# chart.net
KiCad netlist of a schematic drawn in EAGLE
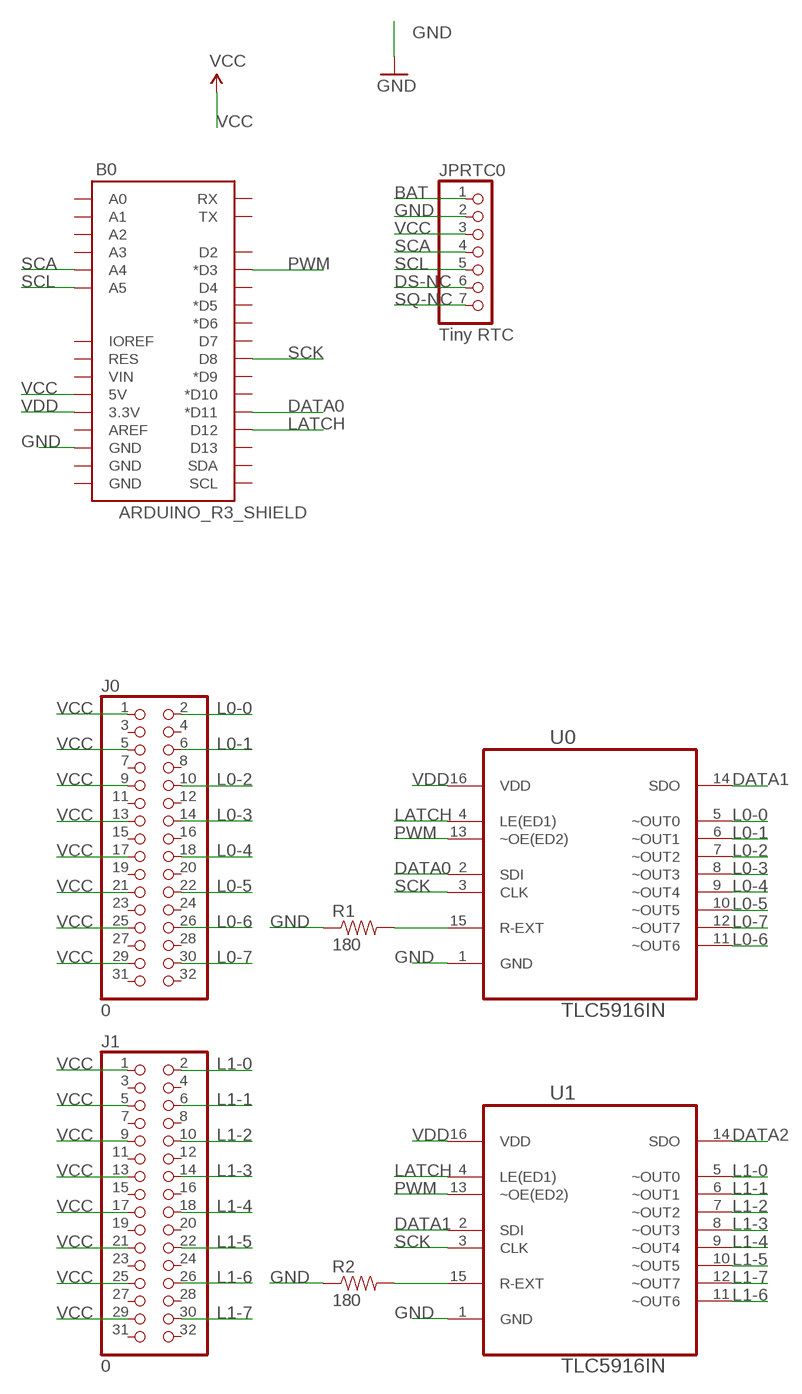
[diagram p0: schematic, sheet 1]

(export (version "E")
  (design (tool "Eeschema 10.0.6"))
  (components
    (comp (ref "B0")
      (value "ARDUINO_R3_SHIELD")
      (footprint "eagle-import:UNO_R3_SHIELD")
      (libsource (lib "eagle-import") (part "ARDUINO_R3_SHIELD"))
    )
    (comp (ref "J0")
      (value "0")
      (footprint "eagle-import:2X16")
      (libsource (lib "eagle-import") (part "PINHD-2X16"))
    )
    (comp (ref "J1")
      (value "0")
      (footprint "eagle-import:2X16")
      (libsource (lib "eagle-import") (part "PINHD-2X16"))
    )
    (comp (ref "JPRTC0")
      (value "Tiny RTC")
      (footprint "eagle-import:1X07")
      (libsource (lib "eagle-import") (part "PINHD-1X7"))
    )
    (comp (ref "R1")
      (value "180")
      (footprint "eagle-import:AXIAL-0.4")
      (libsource (lib "eagle-import") (part "RESISTORPTH-1/4W"))
    )
    (comp (ref "R2")
      (value "180")
      (footprint "eagle-import:AXIAL-0.4")
      (libsource (lib "eagle-import") (part "RESISTORPTH-1/4W"))
    )
    (comp (ref "U0")
      (value "TLC5916IN")
      (footprint "eagle-import:DIP254P762X508-16")
      (libsource (lib "eagle-import") (part "TLC5916IN"))
    )
    (comp (ref "U1")
      (value "TLC5916IN")
      (footprint "eagle-import:DIP254P762X508-16")
      (libsource (lib "eagle-import") (part "TLC5916IN"))
    )
  )
  (nets
    (net (code "1") (name "/BAT") (class "Default")
      (node (ref "JPRTC0") (pin "1") (pinfunction "1_1") (pintype "passive"))
    )
    (net (code "2") (name "/DATA0") (class "Default")
      (node (ref "B0") (pin "D11") (pinfunction "*D11_D11") (pintype "bidirectional"))
      (node (ref "U0") (pin "2") (pinfunction "SDI_2") (pintype "input"))
    )
    (net (code "3") (name "/DATA1") (class "Default")
      (node (ref "U0") (pin "14") (pinfunction "SDO_14") (pintype "output"))
      (node (ref "U1") (pin "2") (pinfunction "SDI_2") (pintype "input"))
    )
    (net (code "4") (name "/DATA2") (class "Default")
      (node (ref "U1") (pin "14") (pinfunction "SDO_14") (pintype "output"))
    )
    (net (code "5") (name "/DS-NC") (class "Default")
      (node (ref "JPRTC0") (pin "6") (pinfunction "6_6") (pintype "passive"))
    )
    (net (code "6") (name "/L0-0") (class "Default")
      (node (ref "J0") (pin "2") (pinfunction "2_2") (pintype "passive"))
      (node (ref "U0") (pin "5") (pinfunction "~{OUT0}_5") (pintype "output"))
    )
    (net (code "7") (name "/L0-1") (class "Default")
      (node (ref "J0") (pin "6") (pinfunction "6_6") (pintype "passive"))
      (node (ref "U0") (pin "6") (pinfunction "~{OUT1}_6") (pintype "output"))
    )
    (net (code "8") (name "/L0-2") (class "Default")
      (node (ref "J0") (pin "10") (pinfunction "10_10") (pintype "passive"))
      (node (ref "U0") (pin "7") (pinfunction "~{OUT2}_7") (pintype "output"))
    )
    (net (code "9") (name "/L0-3") (class "Default")
      (node (ref "J0") (pin "14") (pinfunction "14_14") (pintype "passive"))
      (node (ref "U0") (pin "8") (pinfunction "~{OUT3}_8") (pintype "output"))
    )
    (net (code "10") (name "/L0-4") (class "Default")
      (node (ref "J0") (pin "18") (pinfunction "18_18") (pintype "passive"))
      (node (ref "U0") (pin "9") (pinfunction "~{OUT4}_9") (pintype "output"))
    )
    (net (code "11") (name "/L0-5") (class "Default")
      (node (ref "J0") (pin "22") (pinfunction "22_22") (pintype "passive"))
      (node (ref "U0") (pin "10") (pinfunction "~{OUT5}_10") (pintype "output"))
    )
    (net (code "12") (name "/L0-6") (class "Default")
      (node (ref "J0") (pin "26") (pinfunction "26_26") (pintype "passive"))
      (node (ref "U0") (pin "11") (pinfunction "~{OUT6}_11") (pintype "output"))
    )
    (net (code "13") (name "/L0-7") (class "Default")
      (node (ref "J0") (pin "30") (pinfunction "30_30") (pintype "passive"))
      (node (ref "U0") (pin "12") (pinfunction "~{OUT7}_12") (pintype "output"))
    )
    (net (code "14") (name "/L1-0") (class "Default")
      (node (ref "J1") (pin "2") (pinfunction "2_2") (pintype "passive"))
      (node (ref "U1") (pin "5") (pinfunction "~{OUT0}_5") (pintype "output"))
    )
    (net (code "15") (name "/L1-1") (class "Default")
      (node (ref "J1") (pin "6") (pinfunction "6_6") (pintype "passive"))
      (node (ref "U1") (pin "6") (pinfunction "~{OUT1}_6") (pintype "output"))
    )
    (net (code "16") (name "/L1-2") (class "Default")
      (node (ref "J1") (pin "10") (pinfunction "10_10") (pintype "passive"))
      (node (ref "U1") (pin "7") (pinfunction "~{OUT2}_7") (pintype "output"))
    )
    (net (code "17") (name "/L1-3") (class "Default")
      (node (ref "J1") (pin "14") (pinfunction "14_14") (pintype "passive"))
      (node (ref "U1") (pin "8") (pinfunction "~{OUT3}_8") (pintype "output"))
    )
    (net (code "18") (name "/L1-4") (class "Default")
      (node (ref "J1") (pin "18") (pinfunction "18_18") (pintype "passive"))
      (node (ref "U1") (pin "9") (pinfunction "~{OUT4}_9") (pintype "output"))
    )
    (net (code "19") (name "/L1-5") (class "Default")
      (node (ref "J1") (pin "22") (pinfunction "22_22") (pintype "passive"))
      (node (ref "U1") (pin "10") (pinfunction "~{OUT5}_10") (pintype "output"))
    )
    (net (code "20") (name "/L1-6") (class "Default")
      (node (ref "J1") (pin "26") (pinfunction "26_26") (pintype "passive"))
      (node (ref "U1") (pin "11") (pinfunction "~{OUT6}_11") (pintype "output"))
    )
    (net (code "21") (name "/L1-7") (class "Default")
      (node (ref "J1") (pin "30") (pinfunction "30_30") (pintype "passive"))
      (node (ref "U1") (pin "12") (pinfunction "~{OUT7}_12") (pintype "output"))
    )
    (net (code "22") (name "/LATCH") (class "Default")
      (node (ref "B0") (pin "D12") (pinfunction "D12_D12") (pintype "bidirectional"))
      (node (ref "U0") (pin "4") (pinfunction "LE(ED1)_4") (pintype "input"))
      (node (ref "U1") (pin "4") (pinfunction "LE(ED1)_4") (pintype "input"))
    )
    (net (code "23") (name "/PWM") (class "Default")
      (node (ref "B0") (pin "D3") (pinfunction "*D3_D3") (pintype "bidirectional"))
      (node (ref "U0") (pin "13") (pinfunction "~{OE(ED2})_13") (pintype "input"))
      (node (ref "U1") (pin "13") (pinfunction "~{OE(ED2})_13") (pintype "input"))
    )
    (net (code "24") (name "/SCA") (class "Default")
      (node (ref "B0") (pin "A4") (pinfunction "A4_A4") (pintype "bidirectional"))
      (node (ref "JPRTC0") (pin "4") (pinfunction "4_4") (pintype "passive"))
    )
    (net (code "25") (name "/SCK") (class "Default")
      (node (ref "B0") (pin "D8") (pinfunction "D8_D8") (pintype "bidirectional"))
      (node (ref "U0") (pin "3") (pinfunction "CLK_3") (pintype "input"))
      (node (ref "U1") (pin "3") (pinfunction "CLK_3") (pintype "input"))
    )
    (net (code "26") (name "/SCL") (class "Default")
      (node (ref "B0") (pin "A5") (pinfunction "A5_A5") (pintype "bidirectional"))
      (node (ref "JPRTC0") (pin "5") (pinfunction "5_5") (pintype "passive"))
    )
    (net (code "27") (name "/SQ-NC") (class "Default")
      (node (ref "JPRTC0") (pin "7") (pinfunction "7_7") (pintype "passive"))
    )
    (net (code "28") (name "/VDD") (class "Default")
      (node (ref "B0") (pin "3.3V") (pinfunction "3.3V_3.3V") (pintype "bidirectional"))
      (node (ref "U0") (pin "16") (pinfunction "VDD_16") (pintype "power_in"))
      (node (ref "U1") (pin "16") (pinfunction "VDD_16") (pintype "power_in"))
    )
    (net (code "29") (name "GND") (class "Default")
      (node (ref "B0") (pin "GND@2") (pinfunction "GND_GND@2") (pintype "bidirectional"))
      (node (ref "JPRTC0") (pin "2") (pinfunction "2_2") (pintype "passive"))
      (node (ref "R1") (pin "P$1") (pinfunction "1_P$1") (pintype "passive"))
      (node (ref "R2") (pin "P$1") (pinfunction "1_P$1") (pintype "passive"))
      (node (ref "U0") (pin "1") (pinfunction "GND_1") (pintype "passive"))
      (node (ref "U1") (pin "1") (pinfunction "GND_1") (pintype "passive"))
    )
    (net (code "30") (name "Net-(R1-2)") (class "Default")
      (node (ref "R1") (pin "P$2") (pinfunction "2_P$2") (pintype "passive"))
      (node (ref "U0") (pin "15") (pinfunction "R-EXT_15") (pintype "passive"))
    )
    (net (code "31") (name "Net-(R2-2)") (class "Default")
      (node (ref "R2") (pin "P$2") (pinfunction "2_P$2") (pintype "passive"))
      (node (ref "U1") (pin "15") (pinfunction "R-EXT_15") (pintype "passive"))
    )
    (net (code "32") (name "VCC") (class "Default")
      (node (ref "B0") (pin "5V") (pinfunction "5V_5V") (pintype "bidirectional"))
      (node (ref "J0") (pin "1") (pinfunction "1_1") (pintype "passive"))
      (node (ref "J0") (pin "13") (pinfunction "13_13") (pintype "passive"))
      (node (ref "J0") (pin "17") (pinfunction "17_17") (pintype "passive"))
      (node (ref "J0") (pin "21") (pinfunction "21_21") (pintype "passive"))
      (node (ref "J0") (pin "25") (pinfunction "25_25") (pintype "passive"))
      (node (ref "J0") (pin "29") (pinfunction "29_29") (pintype "passive"))
      (node (ref "J0") (pin "5") (pinfunction "5_5") (pintype "passive"))
      (node (ref "J0") (pin "9") (pinfunction "9_9") (pintype "passive"))
      (node (ref "J1") (pin "1") (pinfunction "1_1") (pintype "passive"))
      (node (ref "J1") (pin "13") (pinfunction "13_13") (pintype "passive"))
      (node (ref "J1") (pin "17") (pinfunction "17_17") (pintype "passive"))
      (node (ref "J1") (pin "21") (pinfunction "21_21") (pintype "passive"))
      (node (ref "J1") (pin "25") (pinfunction "25_25") (pintype "passive"))
      (node (ref "J1") (pin "29") (pinfunction "29_29") (pintype "passive"))
      (node (ref "J1") (pin "5") (pinfunction "5_5") (pintype "passive"))
      (node (ref "J1") (pin "9") (pinfunction "9_9") (pintype "passive"))
      (node (ref "JPRTC0") (pin "3") (pinfunction "3_3") (pintype "passive"))
    )
    (net (code "33") (name "unconnected-(B0-*D5-PadD5)") (class "Default")
      (node (ref "B0") (pin "D5") (pinfunction "*D5_D5") (pintype "bidirectional"))
    )
    (net (code "34") (name "unconnected-(B0-*D6-PadD6)") (class "Default")
      (node (ref "B0") (pin "D6") (pinfunction "*D6_D6") (pintype "bidirectional"))
    )
    (net (code "35") (name "unconnected-(B0-*D9-PadD9)") (class "Default")
      (node (ref "B0") (pin "D9") (pinfunction "*D9_D9") (pintype "bidirectional"))
    )
    (net (code "36") (name "unconnected-(B0-*D10-PadD10)") (class "Default")
      (node (ref "B0") (pin "D10") (pinfunction "*D10_D10") (pintype "bidirectional"))
    )
    (net (code "37") (name "unconnected-(B0-GND-PadGND@0)") (class "Default")
      (node (ref "B0") (pin "GND@0") (pinfunction "GND_GND@0") (pintype "bidirectional"))
    )
    (net (code "38") (name "unconnected-(B0-GND-PadGND@1)") (class "Default")
      (node (ref "B0") (pin "GND@1") (pinfunction "GND_GND@1") (pintype "bidirectional"))
    )
    (net (code "39") (name "unconnected-(B0-PadA0)") (class "Default")
      (node (ref "B0") (pin "A0") (pinfunction "A0_A0") (pintype "bidirectional"))
    )
    (net (code "40") (name "unconnected-(B0-PadA1)") (class "Default")
      (node (ref "B0") (pin "A1") (pinfunction "A1_A1") (pintype "bidirectional"))
    )
    (net (code "41") (name "unconnected-(B0-PadA2)") (class "Default")
      (node (ref "B0") (pin "A2") (pinfunction "A2_A2") (pintype "bidirectional"))
    )
    (net (code "42") (name "unconnected-(B0-PadA3)") (class "Default")
      (node (ref "B0") (pin "A3") (pinfunction "A3_A3") (pintype "bidirectional"))
    )
    (net (code "43") (name "unconnected-(B0-PadAREF)") (class "Default")
      (node (ref "B0") (pin "AREF") (pinfunction "AREF_AREF") (pintype "bidirectional"))
    )
    (net (code "44") (name "unconnected-(B0-PadD2)") (class "Default")
      (node (ref "B0") (pin "D2") (pinfunction "D2_D2") (pintype "bidirectional"))
    )
    (net (code "45") (name "unconnected-(B0-PadD4)") (class "Default")
      (node (ref "B0") (pin "D4") (pinfunction "D4_D4") (pintype "bidirectional"))
    )
    (net (code "46") (name "unconnected-(B0-PadD7)") (class "Default")
      (node (ref "B0") (pin "D7") (pinfunction "D7_D7") (pintype "bidirectional"))
    )
    (net (code "47") (name "unconnected-(B0-PadD13)") (class "Default")
      (node (ref "B0") (pin "D13") (pinfunction "D13_D13") (pintype "bidirectional"))
    )
    (net (code "48") (name "unconnected-(B0-PadIOREF)") (class "Default")
      (node (ref "B0") (pin "IOREF") (pinfunction "IOREF_IOREF") (pintype "bidirectional"))
    )
    (net (code "49") (name "unconnected-(B0-PadRES)") (class "Default")
      (node (ref "B0") (pin "RES") (pinfunction "RES_RES") (pintype "bidirectional"))
    )
    (net (code "50") (name "unconnected-(B0-PadRX)") (class "Default")
      (node (ref "B0") (pin "RX") (pinfunction "RX_RX") (pintype "bidirectional"))
    )
    (net (code "51") (name "unconnected-(B0-PadSCL)") (class "Default")
      (node (ref "B0") (pin "SCL") (pinfunction "SCL_SCL") (pintype "bidirectional"))
    )
    (net (code "52") (name "unconnected-(B0-PadSDA)") (class "Default")
      (node (ref "B0") (pin "SDA") (pinfunction "SDA_SDA") (pintype "bidirectional"))
    )
    (net (code "53") (name "unconnected-(B0-PadTX)") (class "Default")
      (node (ref "B0") (pin "TX") (pinfunction "TX_TX") (pintype "bidirectional"))
    )
    (net (code "54") (name "unconnected-(B0-PadVIN)") (class "Default")
      (node (ref "B0") (pin "VIN") (pinfunction "VIN_VIN") (pintype "bidirectional"))
    )
    (net (code "55") (name "unconnected-(J0-Pad3)") (class "Default")
      (node (ref "J0") (pin "3") (pinfunction "3_3") (pintype "passive"))
    )
    (net (code "56") (name "unconnected-(J0-Pad4)") (class "Default")
      (node (ref "J0") (pin "4") (pinfunction "4_4") (pintype "passive"))
    )
    (net (code "57") (name "unconnected-(J0-Pad7)") (class "Default")
      (node (ref "J0") (pin "7") (pinfunction "7_7") (pintype "passive"))
    )
    (net (code "58") (name "unconnected-(J0-Pad8)") (class "Default")
      (node (ref "J0") (pin "8") (pinfunction "8_8") (pintype "passive"))
    )
    (net (code "59") (name "unconnected-(J0-Pad11)") (class "Default")
      (node (ref "J0") (pin "11") (pinfunction "11_11") (pintype "passive"))
    )
    (net (code "60") (name "unconnected-(J0-Pad12)") (class "Default")
      (node (ref "J0") (pin "12") (pinfunction "12_12") (pintype "passive"))
    )
    (net (code "61") (name "unconnected-(J0-Pad15)") (class "Default")
      (node (ref "J0") (pin "15") (pinfunction "15_15") (pintype "passive"))
    )
    (net (code "62") (name "unconnected-(J0-Pad16)") (class "Default")
      (node (ref "J0") (pin "16") (pinfunction "16_16") (pintype "passive"))
    )
    (net (code "63") (name "unconnected-(J0-Pad19)") (class "Default")
      (node (ref "J0") (pin "19") (pinfunction "19_19") (pintype "passive"))
    )
    (net (code "64") (name "unconnected-(J0-Pad20)") (class "Default")
      (node (ref "J0") (pin "20") (pinfunction "20_20") (pintype "passive"))
    )
    (net (code "65") (name "unconnected-(J0-Pad23)") (class "Default")
      (node (ref "J0") (pin "23") (pinfunction "23_23") (pintype "passive"))
    )
    (net (code "66") (name "unconnected-(J0-Pad24)") (class "Default")
      (node (ref "J0") (pin "24") (pinfunction "24_24") (pintype "passive"))
    )
    (net (code "67") (name "unconnected-(J0-Pad27)") (class "Default")
      (node (ref "J0") (pin "27") (pinfunction "27_27") (pintype "passive"))
    )
    (net (code "68") (name "unconnected-(J0-Pad28)") (class "Default")
      (node (ref "J0") (pin "28") (pinfunction "28_28") (pintype "passive"))
    )
    (net (code "69") (name "unconnected-(J0-Pad31)") (class "Default")
      (node (ref "J0") (pin "31") (pinfunction "31_31") (pintype "passive"))
    )
    (net (code "70") (name "unconnected-(J0-Pad32)") (class "Default")
      (node (ref "J0") (pin "32") (pinfunction "32_32") (pintype "passive"))
    )
    (net (code "71") (name "unconnected-(J1-Pad3)") (class "Default")
      (node (ref "J1") (pin "3") (pinfunction "3_3") (pintype "passive"))
    )
    (net (code "72") (name "unconnected-(J1-Pad4)") (class "Default")
      (node (ref "J1") (pin "4") (pinfunction "4_4") (pintype "passive"))
    )
    (net (code "73") (name "unconnected-(J1-Pad7)") (class "Default")
      (node (ref "J1") (pin "7") (pinfunction "7_7") (pintype "passive"))
    )
    (net (code "74") (name "unconnected-(J1-Pad8)") (class "Default")
      (node (ref "J1") (pin "8") (pinfunction "8_8") (pintype "passive"))
    )
    (net (code "75") (name "unconnected-(J1-Pad11)") (class "Default")
      (node (ref "J1") (pin "11") (pinfunction "11_11") (pintype "passive"))
    )
    (net (code "76") (name "unconnected-(J1-Pad12)") (class "Default")
      (node (ref "J1") (pin "12") (pinfunction "12_12") (pintype "passive"))
    )
    (net (code "77") (name "unconnected-(J1-Pad15)") (class "Default")
      (node (ref "J1") (pin "15") (pinfunction "15_15") (pintype "passive"))
    )
    (net (code "78") (name "unconnected-(J1-Pad16)") (class "Default")
      (node (ref "J1") (pin "16") (pinfunction "16_16") (pintype "passive"))
    )
    (net (code "79") (name "unconnected-(J1-Pad19)") (class "Default")
      (node (ref "J1") (pin "19") (pinfunction "19_19") (pintype "passive"))
    )
    (net (code "80") (name "unconnected-(J1-Pad20)") (class "Default")
      (node (ref "J1") (pin "20") (pinfunction "20_20") (pintype "passive"))
    )
    (net (code "81") (name "unconnected-(J1-Pad23)") (class "Default")
      (node (ref "J1") (pin "23") (pinfunction "23_23") (pintype "passive"))
    )
    (net (code "82") (name "unconnected-(J1-Pad24)") (class "Default")
      (node (ref "J1") (pin "24") (pinfunction "24_24") (pintype "passive"))
    )
    (net (code "83") (name "unconnected-(J1-Pad27)") (class "Default")
      (node (ref "J1") (pin "27") (pinfunction "27_27") (pintype "passive"))
    )
    (net (code "84") (name "unconnected-(J1-Pad28)") (class "Default")
      (node (ref "J1") (pin "28") (pinfunction "28_28") (pintype "passive"))
    )
    (net (code "85") (name "unconnected-(J1-Pad31)") (class "Default")
      (node (ref "J1") (pin "31") (pinfunction "31_31") (pintype "passive"))
    )
    (net (code "86") (name "unconnected-(J1-Pad32)") (class "Default")
      (node (ref "J1") (pin "32") (pinfunction "32_32") (pintype "passive"))
    )
  )
)
